# HighRangeAccelerometer.net
KiCad netlist of a schematic drawn in EAGLE
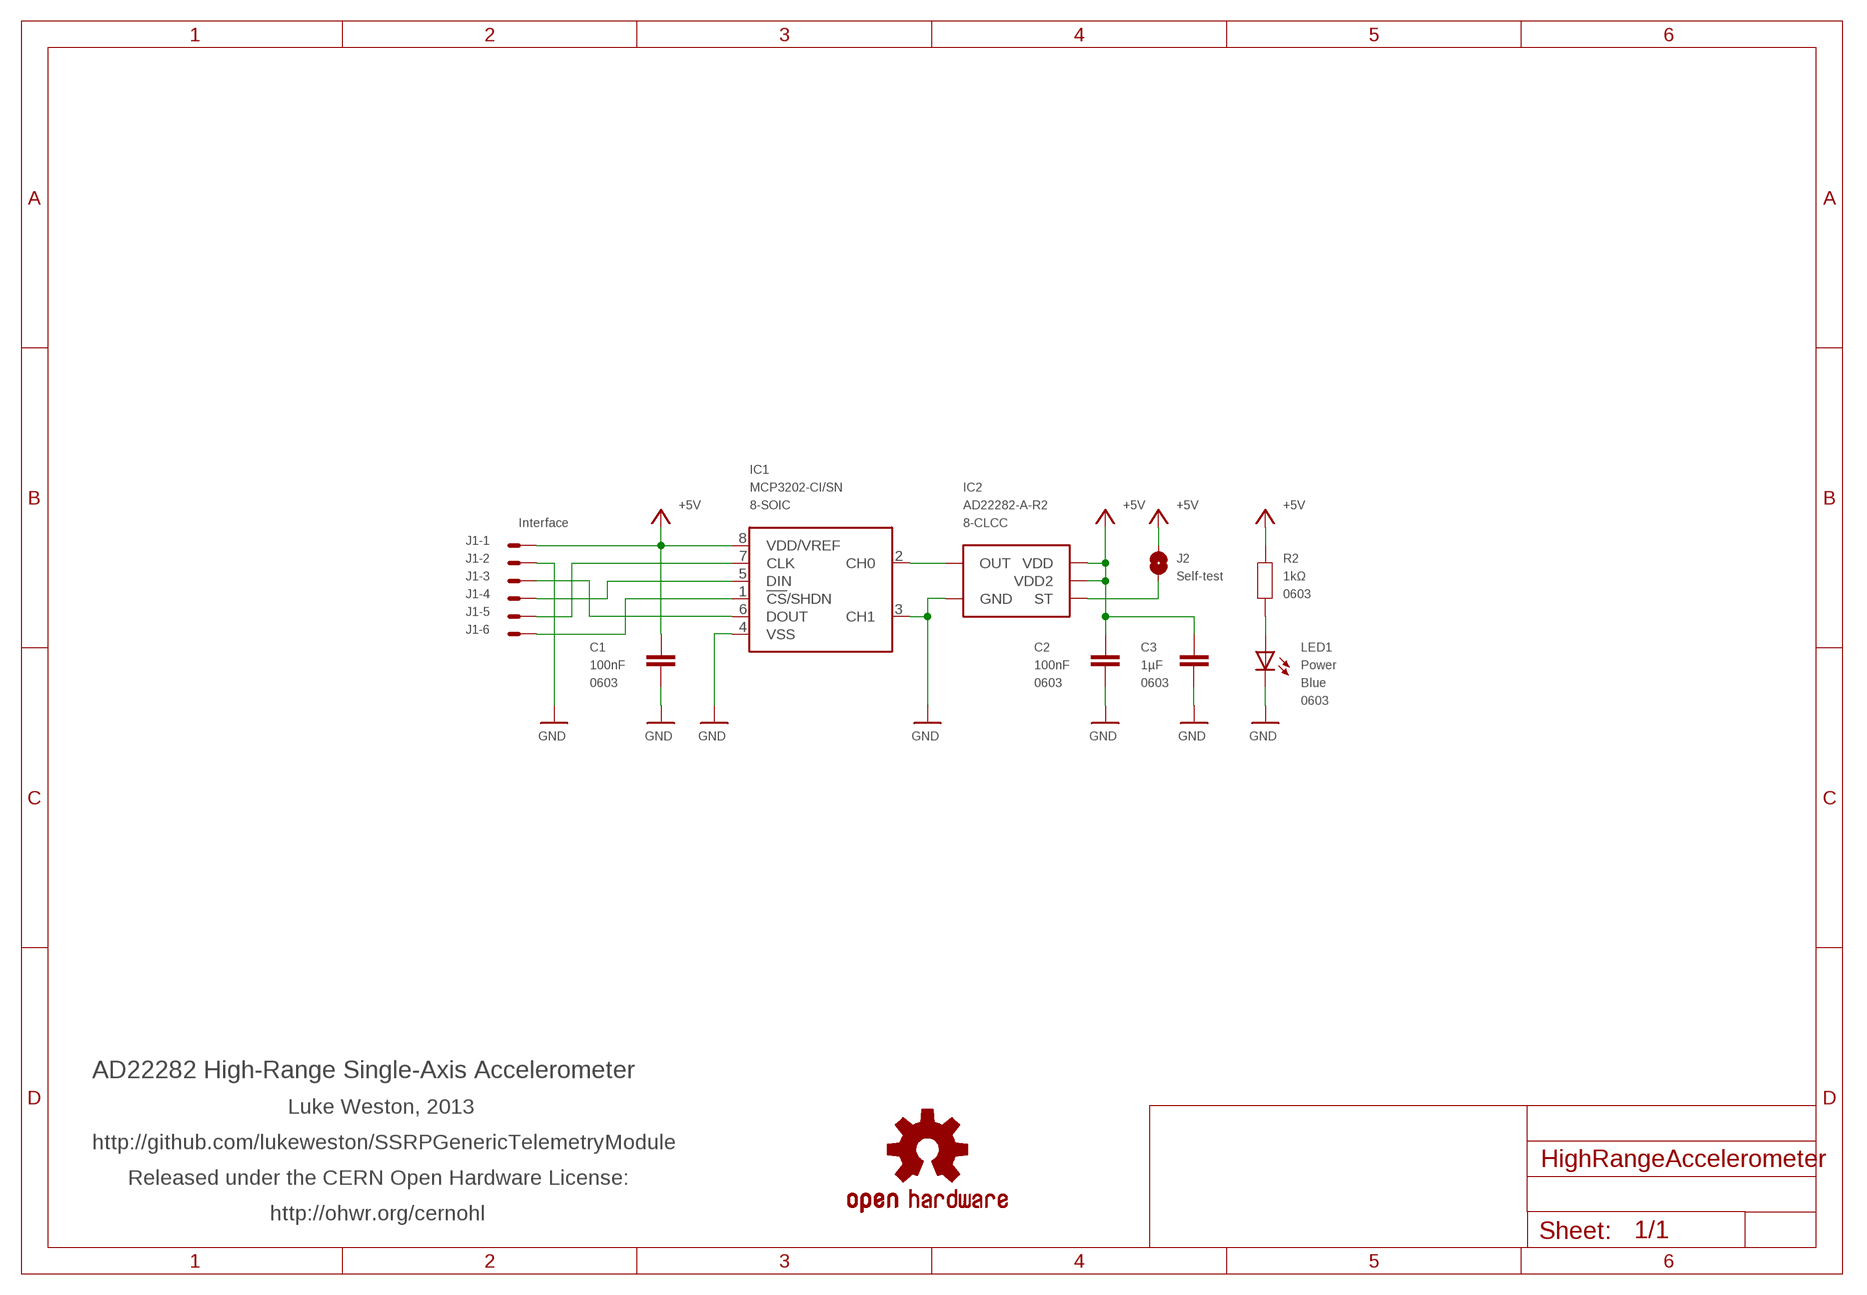
[diagram p0: schematic, sheet 1]

(export (version "E")
  (design (tool "Eeschema 10.0.6"))
  (components
    (comp (ref "C1")
      (value "100nF")
      (footprint "eagle-import:0603")
      (fields (field (name "PACKAGE") "0603"))
      (libsource (lib "eagle-import") (part "CAP0603"))
    )
    (comp (ref "C2")
      (value "100nF")
      (footprint "eagle-import:0603")
      (fields (field (name "PACKAGE") "0603"))
      (libsource (lib "eagle-import") (part "CAP0603"))
    )
    (comp (ref "C3")
      (value "1µF")
      (footprint "eagle-import:0603")
      (fields (field (name "PACKAGE") "0603"))
      (libsource (lib "eagle-import") (part "CAP0603"))
    )
    (comp (ref "IC1")
      (value "MCP3202-CI/SN")
      (footprint "eagle-import:SO-08")
      (fields (field (name "PACKAGE") "8-SOIC"))
      (libsource (lib "eagle-import") (part "MCP3202SN"))
    )
    (comp (ref "IC2")
      (value "AD22282-A-R2")
      (footprint "eagle-import:ADXL193")
      (fields (field (name "PACKAGE") "8-CLCC"))
      (libsource (lib "eagle-import") (part "ADXL193"))
    )
    (comp (ref "J1")
      (value "Interface")
      (footprint "eagle-import:7395-06")
      (libsource (lib "eagle-import") (part "22-?-0605-7068"))
    )
    (comp (ref "J2")
      (value "Self-test")
      (footprint "eagle-import:SJ")
      (libsource (lib "eagle-import") (part "SJ"))
    )
    (comp (ref "LED1")
      (value "Power")
      (footprint "eagle-import:LED-0603")
      (fields (field (name "COLOUR") "Blue") (field (name "PACKAGE") "0603"))
      (libsource (lib "eagle-import") (part "LED0603"))
    )
    (comp (ref "R2")
      (value "1kΩ")
      (footprint "eagle-import:0603")
      (fields (field (name "PACKAGE") "0603"))
      (libsource (lib "eagle-import") (part "RESISTOR0603"))
    )
    (comp (ref "SY")
      (value "OSHW-LOGOS")
      (footprint "eagle-import:OSHW-LOGO-S")
      (libsource (lib "eagle-import") (part "OSHW-LOGOS"))
    )
  )
  (nets
    (net (code "1") (name "+5V") (class "Default")
      (node (ref "C1") (pin "2") (pinfunction "2_2") (pintype "passive"))
      (node (ref "C2") (pin "2") (pinfunction "2_2") (pintype "passive"))
      (node (ref "C3") (pin "2") (pinfunction "2_2") (pintype "passive"))
      (node (ref "IC1") (pin "8") (pinfunction "VDD/VREF_8") (pintype "input"))
      (node (ref "IC2") (pin "P$7") (pinfunction "VDD_P$7") (pintype "bidirectional"))
      (node (ref "IC2") (pin "P$8") (pinfunction "VDD2_P$8") (pintype "bidirectional"))
      (node (ref "J1") (pin "1") (pinfunction "S_1") (pintype "passive"))
      (node (ref "J2") (pin "2") (pinfunction "2_2") (pintype "passive"))
      (node (ref "R2") (pin "2") (pinfunction "2_2") (pintype "passive"))
    )
    (net (code "2") (name "GND") (class "Default")
      (node (ref "C1") (pin "1") (pinfunction "1_1") (pintype "passive"))
      (node (ref "C2") (pin "1") (pinfunction "1_1") (pintype "passive"))
      (node (ref "C3") (pin "1") (pinfunction "1_1") (pintype "passive"))
      (node (ref "IC1") (pin "3") (pinfunction "CH1_3") (pintype "input"))
      (node (ref "IC1") (pin "4") (pinfunction "VSS_4") (pintype "input"))
      (node (ref "IC2") (pin "P$3") (pinfunction "GND_P$3") (pintype "bidirectional"))
      (node (ref "J1") (pin "2") (pinfunction "S_2") (pintype "passive"))
      (node (ref "LED1") (pin "C") (pinfunction "C_C") (pintype "passive"))
    )
    (net (code "3") (name "Net-(IC1-CH0)") (class "Default")
      (node (ref "IC1") (pin "2") (pinfunction "CH0_2") (pintype "input"))
      (node (ref "IC2") (pin "P$6") (pinfunction "OUT_P$6") (pintype "bidirectional"))
    )
    (net (code "4") (name "Net-(IC1-CLK)") (class "Default")
      (node (ref "IC1") (pin "7") (pinfunction "CLK_7") (pintype "input"))
      (node (ref "J1") (pin "5") (pinfunction "S_5") (pintype "passive"))
    )
    (net (code "5") (name "Net-(IC1-DIN)") (class "Default")
      (node (ref "IC1") (pin "5") (pinfunction "DIN_5") (pintype "input"))
      (node (ref "J1") (pin "4") (pinfunction "S_4") (pintype "passive"))
    )
    (net (code "6") (name "Net-(IC1-DOUT)") (class "Default")
      (node (ref "IC1") (pin "6") (pinfunction "DOUT_6") (pintype "input"))
      (node (ref "J1") (pin "3") (pinfunction "S_3") (pintype "passive"))
    )
    (net (code "7") (name "Net-(IC1-~{CS}{slash}SHDN)") (class "Default")
      (node (ref "IC1") (pin "1") (pinfunction "~{CS}/SHDN_1") (pintype "input"))
      (node (ref "J1") (pin "6") (pinfunction "S_6") (pintype "passive"))
    )
    (net (code "8") (name "Net-(IC2-ST)") (class "Default")
      (node (ref "IC2") (pin "P$4") (pinfunction "ST_P$4") (pintype "bidirectional"))
      (node (ref "J2") (pin "1") (pinfunction "1_1") (pintype "passive"))
    )
    (net (code "9") (name "Net-(LED1-PadA)") (class "Default")
      (node (ref "LED1") (pin "A") (pinfunction "A_A") (pintype "passive"))
      (node (ref "R2") (pin "1") (pinfunction "1_1") (pintype "passive"))
    )
  )
)
